# LoRa-E5_mini_v1_0.net
KiCad netlist of a schematic drawn in EAGLE
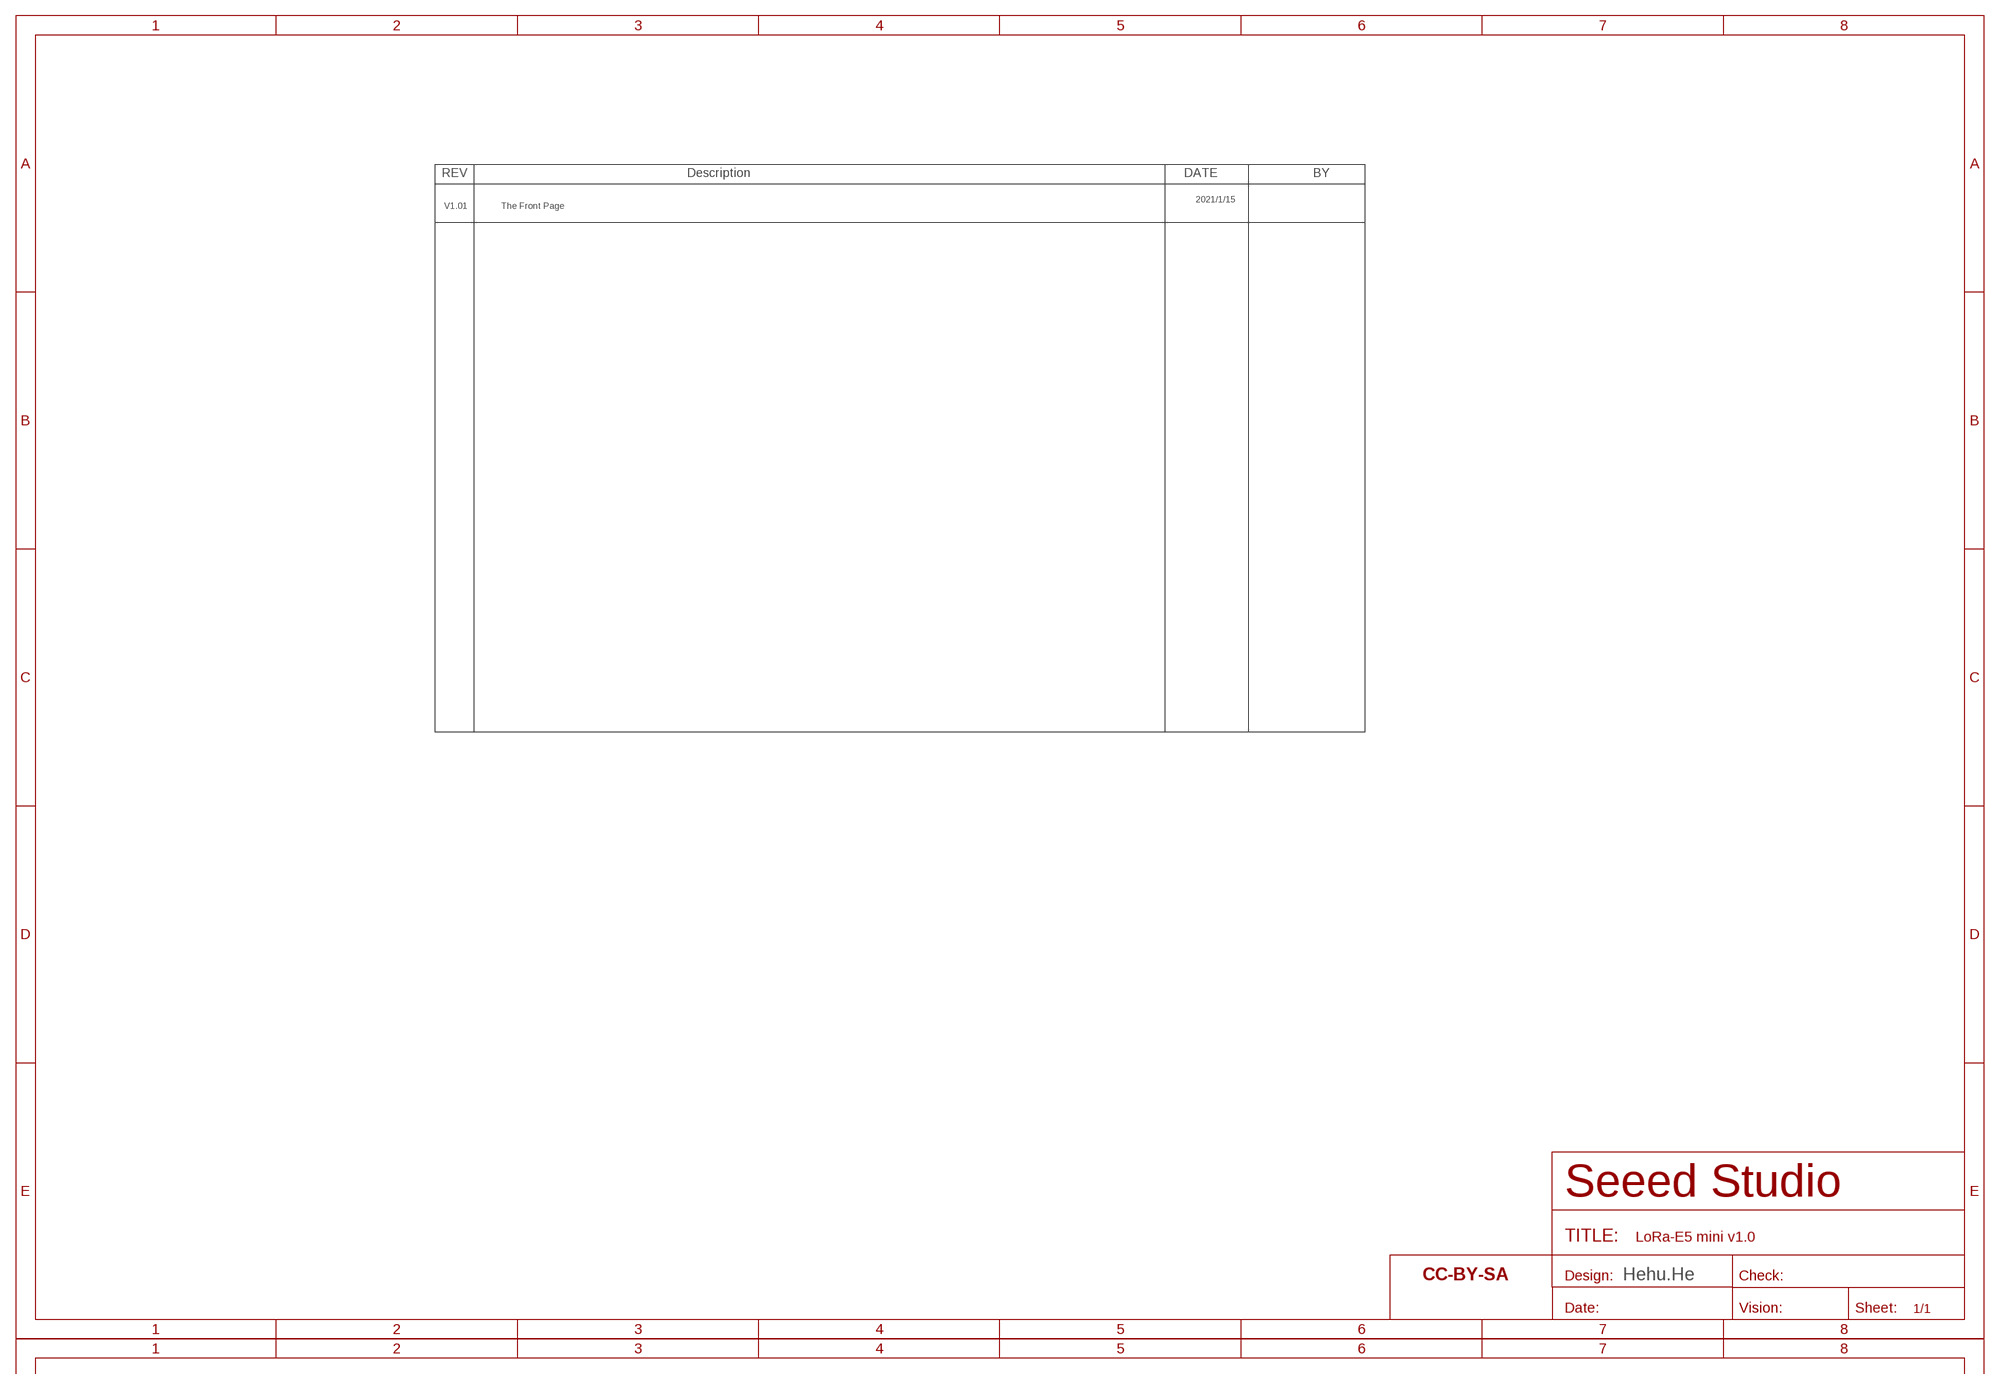
[diagram p0: schematic, sheet 1, part 1 of 2]
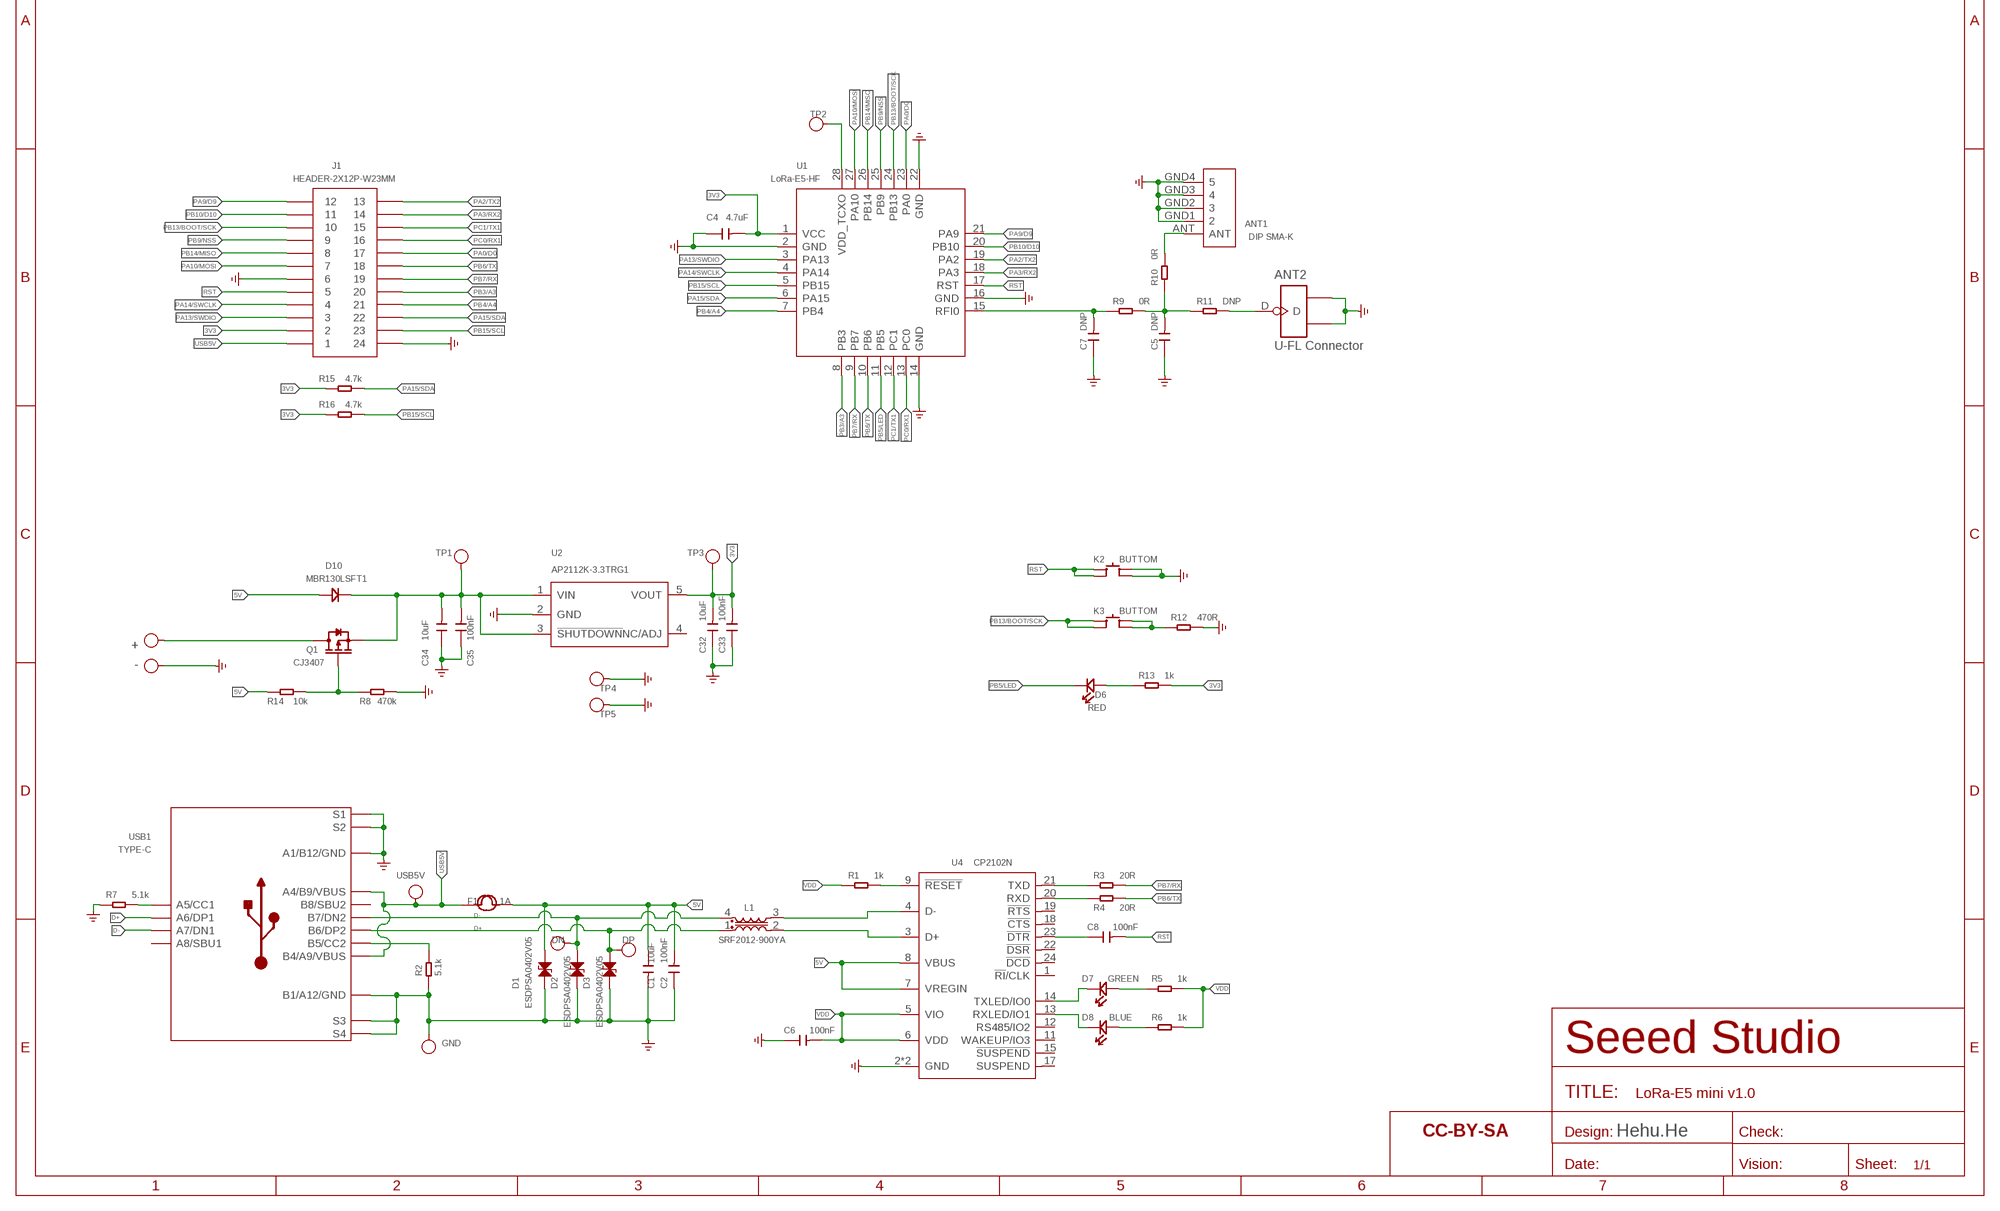
[diagram p1: schematic, sheet 1, part 2 of 2]

(export (version "E")
  (design (tool "Eeschema 10.0.6"))
  (components
    (comp (ref "+")
      (value "TEST-POINT-D65/35")
      (footprint "eagle-import:TP-D65_35MIL")
      (libsource (lib "eagle-import") (part "TEST-POINT-D65/35"))
    )
    (comp (ref "-")
      (value "TEST-POINT-D65/35")
      (footprint "eagle-import:TP-D65_35MIL")
      (libsource (lib "eagle-import") (part "TEST-POINT-D65/35"))
    )
    (comp (ref "ANT1")
      (value "DIP SMA-K")
      (footprint "eagle-import:SMA5P-SMD-5.1-6.5X6.5X16.5MM")
      (libsource (lib "eagle-import") (part "ANTENNA-SMA-MCX-JE-320160125"))
    )
    (comp (ref "ANT2")
      (value "U-FL Connector")
      (footprint "eagle-import:U-FL3P-SMD-2.6X2.6X1.0MM")
      (libsource (lib "eagle-import") (part "ANTENNA-U-FL-320110048"))
    )
    (comp (ref "C1")
      (value "10uF")
      (footprint "eagle-import:C0603")
      (libsource (lib "eagle-import") (part "CAP-0603"))
    )
    (comp (ref "C2")
      (value "100nF")
      (footprint "eagle-import:C0402")
      (libsource (lib "eagle-import") (part "CAP-0402"))
    )
    (comp (ref "C4")
      (value "4.7uF")
      (footprint "eagle-import:C0603")
      (libsource (lib "eagle-import") (part "CAP-0603"))
    )
    (comp (ref "C5")
      (value "DNP")
      (footprint "eagle-import:C0402")
      (libsource (lib "eagle-import") (part "CAP-0402"))
    )
    (comp (ref "C6")
      (value "100nF")
      (footprint "eagle-import:C0402")
      (libsource (lib "eagle-import") (part "CAP-0402"))
    )
    (comp (ref "C7")
      (value "DNP")
      (footprint "eagle-import:C0402")
      (libsource (lib "eagle-import") (part "CAP-0402"))
    )
    (comp (ref "C8")
      (value "100nF")
      (footprint "eagle-import:C0402")
      (libsource (lib "eagle-import") (part "CAP-0402"))
    )
    (comp (ref "C32")
      (value "10uF")
      (footprint "eagle-import:C0805")
      (libsource (lib "eagle-import") (part "CAP-0805"))
    )
    (comp (ref "C33")
      (value "100nF")
      (footprint "eagle-import:C0603")
      (libsource (lib "eagle-import") (part "CAP-0603"))
    )
    (comp (ref "C34")
      (value "10uF")
      (footprint "eagle-import:C0805")
      (libsource (lib "eagle-import") (part "CAP-0805"))
    )
    (comp (ref "C35")
      (value "100nF")
      (footprint "eagle-import:C0603")
      (libsource (lib "eagle-import") (part "CAP-0603"))
    )
    (comp (ref "D1")
      (value "ESDPSA0402V05")
      (footprint "eagle-import:ESD-0402")
      (libsource (lib "eagle-import") (part "D-ESD-2P-DOUBLE-0402"))
    )
    (comp (ref "D2")
      (value "ESDPSA0402V05")
      (footprint "eagle-import:ESD-0402")
      (libsource (lib "eagle-import") (part "D-ESD-2P-DOUBLE-0402"))
    )
    (comp (ref "D3")
      (value "ESDPSA0402V05")
      (footprint "eagle-import:ESD-0402")
      (libsource (lib "eagle-import") (part "D-ESD-2P-DOUBLE-0402"))
    )
    (comp (ref "D6")
      (value "RED")
      (footprint "eagle-import:LED-0603")
      (libsource (lib "eagle-import") (part "LED'0603'"))
    )
    (comp (ref "D7")
      (value "GREEN")
      (footprint "eagle-import:LED-0603")
      (libsource (lib "eagle-import") (part "LED'0603'"))
    )
    (comp (ref "D8")
      (value "BLUE")
      (footprint "eagle-import:LED-0603")
      (libsource (lib "eagle-import") (part "LED'0603'"))
    )
    (comp (ref "D10")
      (value "MBR130LSFT1")
      (footprint "eagle-import:SOD-123")
      (libsource (lib "eagle-import") (part "DIODE'1206'"))
    )
    (comp (ref "DN")
      (value "TEST")
      (footprint "eagle-import:TP-D45MIL")
      (fields (field (name "PARTNO") "DNP"))
      (libsource (lib "eagle-import") (part "TEST-POINT'4545'"))
    )
    (comp (ref "DP")
      (value "TEST")
      (footprint "eagle-import:TP-D45MIL")
      (fields (field (name "PARTNO") "DNP"))
      (libsource (lib "eagle-import") (part "TEST-POINT'4545'"))
    )
    (comp (ref "F1")
      (value "1A")
      (footprint "eagle-import:F1206")
      (libsource (lib "eagle-import") (part "FUSE'1206'"))
    )
    (comp (ref "GND")
      (value "TEST")
      (footprint "eagle-import:TP-D45MIL")
      (fields (field (name "PARTNO") "DNP"))
      (libsource (lib "eagle-import") (part "TEST-POINT'4545'"))
    )
    (comp (ref "J1")
      (value "HEADER-2X12P-W23MM")
      (footprint "eagle-import:H2X12-2.54-23MM")
      (libsource (lib "eagle-import") (part "HEADER-2X12P-W23MM"))
    )
    (comp (ref "K2")
      (value "BUTTOM")
      (footprint "eagle-import:SW4P-SMD-4.5X3.2X2.5MM")
      (libsource (lib "eagle-import") (part "BUTTON-4P-4.5X3.2"))
    )
    (comp (ref "K3")
      (value "BUTTOM")
      (footprint "eagle-import:SW4P-SMD-4.5X3.2X2.5MM")
      (libsource (lib "eagle-import") (part "BUTTON-4P-4.5X3.2"))
    )
    (comp (ref "L1")
      (value "SRF2012-900YA")
      (footprint "eagle-import:INT4-0.85-2X1.25X1.2MM")
      (libsource (lib "eagle-import") (part "INDUCTOR-COMMON-MODE-SRF2012-900YA"))
    )
    (comp (ref "Q1")
      (value "CJ3407")
      (footprint "eagle-import:SOT-23")
      (libsource (lib "eagle-import") (part "MOSFET-P'SI2323CDS/SI2305DS{lt}BR{gt}'"))
    )
    (comp (ref "R1")
      (value "1k")
      (footprint "eagle-import:R0402")
      (libsource (lib "eagle-import") (part "RES-0402"))
    )
    (comp (ref "R2")
      (value "5.1k")
      (footprint "eagle-import:R0402")
      (libsource (lib "eagle-import") (part "RES-0402"))
    )
    (comp (ref "R3")
      (value "20R")
      (footprint "eagle-import:R0402")
      (libsource (lib "eagle-import") (part "RES-0402"))
    )
    (comp (ref "R4")
      (value "20R")
      (footprint "eagle-import:R0402")
      (libsource (lib "eagle-import") (part "RES-0402"))
    )
    (comp (ref "R5")
      (value "1k")
      (footprint "eagle-import:R0402")
      (libsource (lib "eagle-import") (part "RES-0402"))
    )
    (comp (ref "R6")
      (value "1k")
      (footprint "eagle-import:R0402")
      (libsource (lib "eagle-import") (part "RES-0402"))
    )
    (comp (ref "R7")
      (value "5.1k")
      (footprint "eagle-import:R0402")
      (libsource (lib "eagle-import") (part "RES-0402"))
    )
    (comp (ref "R8")
      (value "470k")
      (footprint "eagle-import:R0402")
      (libsource (lib "eagle-import") (part "RES-0402"))
    )
    (comp (ref "R9")
      (value "0R")
      (footprint "eagle-import:R0402")
      (libsource (lib "eagle-import") (part "RES-0402"))
    )
    (comp (ref "R10")
      (value "0R")
      (footprint "eagle-import:R0402")
      (libsource (lib "eagle-import") (part "RES-0402"))
    )
    (comp (ref "R11")
      (value "DNP")
      (footprint "eagle-import:R0402")
      (libsource (lib "eagle-import") (part "RES-0402"))
    )
    (comp (ref "R12")
      (value "470R")
      (footprint "eagle-import:R0402")
      (libsource (lib "eagle-import") (part "RES-0402"))
    )
    (comp (ref "R13")
      (value "1k")
      (footprint "eagle-import:R0402")
      (libsource (lib "eagle-import") (part "RES-0402"))
    )
    (comp (ref "R14")
      (value "10k")
      (footprint "eagle-import:R0402")
      (libsource (lib "eagle-import") (part "RES-0402"))
    )
    (comp (ref "R15")
      (value "4.7k")
      (footprint "eagle-import:R0402")
      (libsource (lib "eagle-import") (part "RES-0402"))
    )
    (comp (ref "R16")
      (value "4.7k")
      (footprint "eagle-import:R0402")
      (libsource (lib "eagle-import") (part "RES-0402"))
    )
    (comp (ref "TP1")
      (value "TEST")
      (footprint "eagle-import:TP-D45MIL")
      (fields (field (name "PARTNO") "DNP"))
      (libsource (lib "eagle-import") (part "TEST-POINT'4545'"))
    )
    (comp (ref "TP2")
      (value "TEST")
      (footprint "eagle-import:TP-D45MIL")
      (fields (field (name "PARTNO") "DNP"))
      (libsource (lib "eagle-import") (part "TEST-POINT'4545'"))
    )
    (comp (ref "TP3")
      (value "TEST")
      (footprint "eagle-import:TP-D45MIL")
      (fields (field (name "PARTNO") "DNP"))
      (libsource (lib "eagle-import") (part "TEST-POINT'4545'"))
    )
    (comp (ref "TP4")
      (value "TEST-POINT-23")
      (footprint "eagle-import:TP-D23MIL")
      (libsource (lib "eagle-import") (part "TEST-POINT-23"))
    )
    (comp (ref "TP5")
      (value "TEST-POINT-23")
      (footprint "eagle-import:TP-D23MIL")
      (libsource (lib "eagle-import") (part "TEST-POINT-23"))
    )
    (comp (ref "U1")
      (value "LoRa-E5-HF")
      (footprint "eagle-import:MOUDLE28P-1.25-12X12X2.5MM")
      (libsource (lib "eagle-import") (part "MOUDLE_LORA_E5"))
    )
    (comp (ref "U2")
      (value "AP2112K-3.3TRG1")
      (footprint "eagle-import:SOT-23-5")
      (libsource (lib "eagle-import") (part "PMIC-AP2127"))
    )
    (comp (ref "U4")
      (value "CP2102N")
      (footprint "eagle-import:QFN24G-0.5-4X4MM")
      (libsource (lib "eagle-import") (part "CONVERTER-CP2102N(QFN24)"))
    )
    (comp (ref "USB1")
      (value "TYPE-C")
      (footprint "eagle-import:USB2.0-TYPE-C")
      (libsource (lib "eagle-import") (part "USB2.0-TYPE-C-320010698"))
    )
    (comp (ref "USB5V")
      (value "TEST")
      (footprint "eagle-import:TP-D45MIL")
      (fields (field (name "PARTNO") "DNP"))
      (libsource (lib "eagle-import") (part "TEST-POINT'4545'"))
    )
  )
  (nets
    (net (code "1") (name "3V3") (class "Default")
      (node (ref "C32") (pin "2") (pinfunction "2_2") (pintype "passive"))
      (node (ref "C33") (pin "2") (pinfunction "2_2") (pintype "passive"))
      (node (ref "C4") (pin "2") (pinfunction "2_2") (pintype "passive"))
      (node (ref "J1") (pin "A2") (pinfunction "2_A2") (pintype "bidirectional"))
      (node (ref "J1") (pin "B2") (pinfunction "2_B2") (pintype "bidirectional"))
      (node (ref "J1") (pin "E2") (pinfunction "2_E2") (pintype "bidirectional"))
      (node (ref "J1") (pin "F2") (pinfunction "2_F2") (pintype "bidirectional"))
      (node (ref "R13") (pin "2") (pinfunction "2_2") (pintype "passive"))
      (node (ref "R15") (pin "1") (pinfunction "1_1") (pintype "passive"))
      (node (ref "R16") (pin "1") (pinfunction "1_1") (pintype "passive"))
      (node (ref "TP3") (pin "T") (pinfunction "T_T") (pintype "bidirectional"))
      (node (ref "U1") (pin "1") (pinfunction "VCC_1") (pintype "bidirectional"))
      (node (ref "U2") (pin "5") (pinfunction "VOUT_5") (pintype "bidirectional"))
    )
    (net (code "2") (name "5V") (class "Default")
      (node (ref "C1") (pin "1") (pinfunction "1_1") (pintype "passive"))
      (node (ref "C2") (pin "2") (pinfunction "2_2") (pintype "passive"))
      (node (ref "D1") (pin "2") (pinfunction "2_2") (pintype "bidirectional"))
      (node (ref "D10") (pin "+") (pinfunction "+_+") (pintype "passive"))
      (node (ref "F1") (pin "2") (pinfunction "2_2") (pintype "bidirectional"))
      (node (ref "R14") (pin "1") (pinfunction "1_1") (pintype "passive"))
      (node (ref "U4") (pin "7") (pinfunction "VREGIN_7") (pintype "bidirectional"))
      (node (ref "U4") (pin "8") (pinfunction "VBUS_8") (pintype "bidirectional"))
    )
    (net (code "3") (name "D+") (class "Default")
      (node (ref "D3") (pin "2") (pinfunction "2_2") (pintype "bidirectional"))
      (node (ref "DP") (pin "T") (pinfunction "T_T") (pintype "bidirectional"))
      (node (ref "L1") (pin "1") (pinfunction "1_1") (pintype "bidirectional"))
      (node (ref "USB1") (pin "A6") (pinfunction "A6/DP1_A6") (pintype "bidirectional"))
      (node (ref "USB1") (pin "B6") (pinfunction "B6/DP2_B6") (pintype "bidirectional"))
    )
    (net (code "4") (name "D-") (class "Default")
      (node (ref "D2") (pin "2") (pinfunction "2_2") (pintype "bidirectional"))
      (node (ref "DN") (pin "T") (pinfunction "T_T") (pintype "bidirectional"))
      (node (ref "L1") (pin "4") (pinfunction "4_4") (pintype "bidirectional"))
      (node (ref "USB1") (pin "A7") (pinfunction "A7/DN1_A7") (pintype "bidirectional"))
      (node (ref "USB1") (pin "B7") (pinfunction "B7/DN2_B7") (pintype "bidirectional"))
    )
    (net (code "5") (name "GND_POWER") (class "Default")
      (node (ref "-") (pin "P1") (pinfunction "T_P1") (pintype "bidirectional"))
      (node (ref "ANT1") (pin "GND1") (pinfunction "2_GND1") (pintype "bidirectional"))
      (node (ref "ANT1") (pin "GND2") (pinfunction "3_GND2") (pintype "bidirectional"))
      (node (ref "ANT1") (pin "GND3") (pinfunction "4_GND3") (pintype "bidirectional"))
      (node (ref "ANT1") (pin "GND4") (pinfunction "5_GND4") (pintype "bidirectional"))
      (node (ref "ANT2") (pin "GND1") (pinfunction "GND1_GND1") (pintype "bidirectional"))
      (node (ref "ANT2") (pin "GND2") (pinfunction "GND2_GND2") (pintype "bidirectional"))
      (node (ref "C1") (pin "2") (pinfunction "2_2") (pintype "passive"))
      (node (ref "C2") (pin "1") (pinfunction "1_1") (pintype "passive"))
      (node (ref "C32") (pin "1") (pinfunction "1_1") (pintype "passive"))
      (node (ref "C33") (pin "1") (pinfunction "1_1") (pintype "passive"))
      (node (ref "C34") (pin "1") (pinfunction "1_1") (pintype "passive"))
      (node (ref "C35") (pin "1") (pinfunction "1_1") (pintype "passive"))
      (node (ref "C4") (pin "1") (pinfunction "1_1") (pintype "passive"))
      (node (ref "C5") (pin "1") (pinfunction "1_1") (pintype "passive"))
      (node (ref "C6") (pin "1") (pinfunction "1_1") (pintype "passive"))
      (node (ref "C7") (pin "1") (pinfunction "1_1") (pintype "passive"))
      (node (ref "D1") (pin "1") (pinfunction "1_1") (pintype "bidirectional"))
      (node (ref "D2") (pin "1") (pinfunction "1_1") (pintype "bidirectional"))
      (node (ref "D3") (pin "1") (pinfunction "1_1") (pintype "bidirectional"))
      (node (ref "GND") (pin "T") (pinfunction "T_T") (pintype "bidirectional"))
      (node (ref "J1") (pin "A6") (pinfunction "6_A6") (pintype "bidirectional"))
      (node (ref "J1") (pin "B6") (pinfunction "6_B6") (pintype "bidirectional"))
      (node (ref "J1") (pin "C12") (pinfunction "24_C12") (pintype "bidirectional"))
      (node (ref "J1") (pin "D12") (pinfunction "24_D12") (pintype "bidirectional"))
      (node (ref "J1") (pin "E24") (pinfunction "24_E24") (pintype "bidirectional"))
      (node (ref "J1") (pin "E6") (pinfunction "6_E6") (pintype "bidirectional"))
      (node (ref "J1") (pin "F24") (pinfunction "24_F24") (pintype "bidirectional"))
      (node (ref "J1") (pin "F6") (pinfunction "6_F6") (pintype "bidirectional"))
      (node (ref "K2") (pin "3") (pinfunction "B0_3") (pintype "bidirectional"))
      (node (ref "K2") (pin "4") (pinfunction "B1_4") (pintype "bidirectional"))
      (node (ref "R12") (pin "2") (pinfunction "2_2") (pintype "passive"))
      (node (ref "R2") (pin "1") (pinfunction "1_1") (pintype "passive"))
      (node (ref "R7") (pin "1") (pinfunction "1_1") (pintype "passive"))
      (node (ref "R8") (pin "1") (pinfunction "1_1") (pintype "passive"))
      (node (ref "TP4") (pin "T") (pinfunction "T_T") (pintype "bidirectional"))
      (node (ref "TP5") (pin "T") (pinfunction "T_T") (pintype "bidirectional"))
      (node (ref "U1") (pin "14") (pinfunction "GND_14") (pintype "bidirectional"))
      (node (ref "U1") (pin "16") (pinfunction "GND_16") (pintype "bidirectional"))
      (node (ref "U1") (pin "2") (pinfunction "GND_2") (pintype "bidirectional"))
      (node (ref "U1") (pin "22") (pinfunction "GND_22") (pintype "bidirectional"))
      (node (ref "U2") (pin "2") (pinfunction "GND_2") (pintype "bidirectional"))
      (node (ref "U4") (pin "2") (pinfunction "GND_2") (pintype "bidirectional"))
      (node (ref "U4") (pin "PAD") (pinfunction "GND_PAD") (pintype "bidirectional"))
      (node (ref "USB1") (pin "A1_B12") (pinfunction "A1/B12/GND_A1_B12") (pintype "bidirectional"))
      (node (ref "USB1") (pin "B1_A12") (pinfunction "B1/A12/GND_B1_A12") (pintype "bidirectional"))
      (node (ref "USB1") (pin "S1") (pinfunction "S1_S1") (pintype "bidirectional"))
      (node (ref "USB1") (pin "S2") (pinfunction "S2_S2") (pintype "bidirectional"))
      (node (ref "USB1") (pin "S3") (pinfunction "S3_S3") (pintype "bidirectional"))
      (node (ref "USB1") (pin "S4") (pinfunction "S4_S4") (pintype "bidirectional"))
      (node (ref "USB1") (pin "S5") (pinfunction "S1_S5") (pintype "bidirectional"))
      (node (ref "USB1") (pin "S6") (pinfunction "S2_S6") (pintype "bidirectional"))
    )
    (net (code "6") (name "Net-(+-T)") (class "Default")
      (node (ref "+") (pin "P1") (pinfunction "T_P1") (pintype "bidirectional"))
      (node (ref "Q1") (pin "3") (pinfunction "D_3") (pintype "passive"))
    )
    (net (code "7") (name "Net-(ANT1-PadANT)") (class "Default")
      (node (ref "ANT1") (pin "ANT") (pinfunction "ANT_ANT") (pintype "bidirectional"))
      (node (ref "R10") (pin "2") (pinfunction "2_2") (pintype "passive"))
    )
    (net (code "8") (name "Net-(ANT2-PadD)") (class "Default")
      (node (ref "ANT2") (pin "D") (pinfunction "D_D") (pintype "bidirectional"))
      (node (ref "R11") (pin "2") (pinfunction "2_2") (pintype "passive"))
    )
    (net (code "9") (name "Net-(C5-Pad2)") (class "Default")
      (node (ref "C5") (pin "2") (pinfunction "2_2") (pintype "passive"))
      (node (ref "R10") (pin "1") (pinfunction "1_1") (pintype "passive"))
      (node (ref "R11") (pin "1") (pinfunction "1_1") (pintype "passive"))
      (node (ref "R9") (pin "2") (pinfunction "2_2") (pintype "passive"))
    )
    (net (code "10") (name "Net-(D6-Pad+)") (class "Default")
      (node (ref "D6") (pin "+") (pinfunction "+_+") (pintype "passive"))
      (node (ref "R13") (pin "1") (pinfunction "1_1") (pintype "passive"))
    )
    (net (code "11") (name "Net-(D7-Pad+)") (class "Default")
      (node (ref "D7") (pin "+") (pinfunction "+_+") (pintype "passive"))
      (node (ref "R5") (pin "1") (pinfunction "1_1") (pintype "passive"))
    )
    (net (code "12") (name "Net-(D8-Pad+)") (class "Default")
      (node (ref "D8") (pin "+") (pinfunction "+_+") (pintype "passive"))
      (node (ref "R6") (pin "1") (pinfunction "1_1") (pintype "passive"))
    )
    (net (code "13") (name "Net-(K3-B0)") (class "Default")
      (node (ref "K3") (pin "3") (pinfunction "B0_3") (pintype "bidirectional"))
      (node (ref "K3") (pin "4") (pinfunction "B1_4") (pintype "bidirectional"))
      (node (ref "R12") (pin "1") (pinfunction "1_1") (pintype "passive"))
    )
    (net (code "14") (name "Net-(Q1-G)") (class "Default")
      (node (ref "Q1") (pin "1") (pinfunction "G_1") (pintype "passive"))
      (node (ref "R14") (pin "2") (pinfunction "2_2") (pintype "passive"))
      (node (ref "R8") (pin "2") (pinfunction "2_2") (pintype "passive"))
    )
    (net (code "15") (name "Net-(Q1-S)") (class "Default")
      (node (ref "C34") (pin "2") (pinfunction "2_2") (pintype "passive"))
      (node (ref "C35") (pin "2") (pinfunction "2_2") (pintype "passive"))
      (node (ref "D10") (pin "-") (pinfunction "-_-") (pintype "passive"))
      (node (ref "Q1") (pin "2") (pinfunction "S_2") (pintype "passive"))
      (node (ref "TP1") (pin "T") (pinfunction "T_T") (pintype "bidirectional"))
      (node (ref "U2") (pin "1") (pinfunction "VIN_1") (pintype "bidirectional"))
      (node (ref "U2") (pin "3") (pinfunction "~{SHUTDOWN}_3") (pintype "bidirectional"))
    )
    (net (code "16") (name "Net-(U1-RFI0)") (class "Default")
      (node (ref "C7") (pin "2") (pinfunction "2_2") (pintype "passive"))
      (node (ref "R9") (pin "1") (pinfunction "1_1") (pintype "passive"))
      (node (ref "U1") (pin "15") (pinfunction "RFI0_15") (pintype "bidirectional"))
    )
    (net (code "17") (name "Net-(U1-VDD_TCXO)") (class "Default")
      (node (ref "TP2") (pin "T") (pinfunction "T_T") (pintype "bidirectional"))
      (node (ref "U1") (pin "28") (pinfunction "VDD_TCXO_28") (pintype "bidirectional"))
    )
    (net (code "18") (name "Net-(U4-D+)") (class "Default")
      (node (ref "L1") (pin "2") (pinfunction "2_2") (pintype "bidirectional"))
      (node (ref "U4") (pin "3") (pinfunction "D+_3") (pintype "bidirectional"))
    )
    (net (code "19") (name "Net-(U4-D-)") (class "Default")
      (node (ref "L1") (pin "3") (pinfunction "3_3") (pintype "bidirectional"))
      (node (ref "U4") (pin "4") (pinfunction "D-_4") (pintype "bidirectional"))
    )
    (net (code "20") (name "Net-(U4-RXD)") (class "Default")
      (node (ref "R4") (pin "1") (pinfunction "1_1") (pintype "passive"))
      (node (ref "U4") (pin "20") (pinfunction "RXD_20") (pintype "bidirectional"))
    )
    (net (code "21") (name "Net-(U4-RXLED{slash}IO1)") (class "Default")
      (node (ref "D8") (pin "-") (pinfunction "-_-") (pintype "passive"))
      (node (ref "U4") (pin "13") (pinfunction "RXLED/IO1_13") (pintype "bidirectional"))
    )
    (net (code "22") (name "Net-(U4-TXD)") (class "Default")
      (node (ref "R3") (pin "1") (pinfunction "1_1") (pintype "passive"))
      (node (ref "U4") (pin "21") (pinfunction "TXD_21") (pintype "bidirectional"))
    )
    (net (code "23") (name "Net-(U4-TXLED{slash}IO0)") (class "Default")
      (node (ref "D7") (pin "-") (pinfunction "-_-") (pintype "passive"))
      (node (ref "U4") (pin "14") (pinfunction "TXLED/IO0_14") (pintype "bidirectional"))
    )
    (net (code "24") (name "Net-(U4-~{DTR})") (class "Default")
      (node (ref "C8") (pin "1") (pinfunction "1_1") (pintype "passive"))
      (node (ref "U4") (pin "23") (pinfunction "~{DTR}_23") (pintype "bidirectional"))
    )
    (net (code "25") (name "Net-(U4-~{RESET})") (class "Default")
      (node (ref "R1") (pin "2") (pinfunction "2_2") (pintype "passive"))
      (node (ref "U4") (pin "9") (pinfunction "~{RESET}_9") (pintype "bidirectional"))
    )
    (net (code "26") (name "Net-(USB1-A5{slash}CC1)") (class "Default")
      (node (ref "R7") (pin "2") (pinfunction "2_2") (pintype "passive"))
      (node (ref "USB1") (pin "A5") (pinfunction "A5/CC1_A5") (pintype "bidirectional"))
    )
    (net (code "27") (name "Net-(USB1-B5{slash}CC2)") (class "Default")
      (node (ref "R2") (pin "2") (pinfunction "2_2") (pintype "passive"))
      (node (ref "USB1") (pin "B5") (pinfunction "B5/CC2_B5") (pintype "bidirectional"))
    )
    (net (code "28") (name "PA0{slash}D0") (class "Default")
      (node (ref "J1") (pin "C5") (pinfunction "17_C5") (pintype "bidirectional"))
      (node (ref "J1") (pin "D5") (pinfunction "17_D5") (pintype "bidirectional"))
      (node (ref "J1") (pin "E17") (pinfunction "17_E17") (pintype "bidirectional"))
      (node (ref "J1") (pin "F17") (pinfunction "17_F17") (pintype "bidirectional"))
      (node (ref "U1") (pin "23") (pinfunction "PA0_23") (pintype "bidirectional"))
    )
    (net (code "29") (name "PA2{slash}TX2") (class "Default")
      (node (ref "J1") (pin "C1") (pinfunction "13_C1") (pintype "bidirectional"))
      (node (ref "J1") (pin "D1") (pinfunction "13_D1") (pintype "bidirectional"))
      (node (ref "J1") (pin "E13") (pinfunction "13_E13") (pintype "bidirectional"))
      (node (ref "J1") (pin "F13") (pinfunction "13_F13") (pintype "bidirectional"))
      (node (ref "U1") (pin "19") (pinfunction "PA2_19") (pintype "bidirectional"))
    )
    (net (code "30") (name "PA3{slash}RX2") (class "Default")
      (node (ref "J1") (pin "C2") (pinfunction "14_C2") (pintype "bidirectional"))
      (node (ref "J1") (pin "D2") (pinfunction "14_D2") (pintype "bidirectional"))
      (node (ref "J1") (pin "E14") (pinfunction "14_E14") (pintype "bidirectional"))
      (node (ref "J1") (pin "F14") (pinfunction "14_F14") (pintype "bidirectional"))
      (node (ref "U1") (pin "18") (pinfunction "PA3_18") (pintype "bidirectional"))
    )
    (net (code "31") (name "PA9{slash}D9") (class "Default")
      (node (ref "J1") (pin "A12") (pinfunction "12_A12") (pintype "bidirectional"))
      (node (ref "J1") (pin "B12") (pinfunction "12_B12") (pintype "bidirectional"))
      (node (ref "J1") (pin "E12") (pinfunction "12_E12") (pintype "bidirectional"))
      (node (ref "J1") (pin "F12") (pinfunction "12_F12") (pintype "bidirectional"))
      (node (ref "U1") (pin "21") (pinfunction "PA9_21") (pintype "bidirectional"))
    )
    (net (code "32") (name "PA10{slash}MOSI") (class "Default")
      (node (ref "J1") (pin "A7") (pinfunction "7_A7") (pintype "bidirectional"))
      (node (ref "J1") (pin "B7") (pinfunction "7_B7") (pintype "bidirectional"))
      (node (ref "J1") (pin "E7") (pinfunction "7_E7") (pintype "bidirectional"))
      (node (ref "J1") (pin "F7") (pinfunction "7_F7") (pintype "bidirectional"))
      (node (ref "U1") (pin "27") (pinfunction "PA10_27") (pintype "bidirectional"))
    )
    (net (code "33") (name "PA13{slash}SWDIO") (class "Default")
      (node (ref "J1") (pin "A3") (pinfunction "3_A3") (pintype "bidirectional"))
      (node (ref "J1") (pin "B3") (pinfunction "3_B3") (pintype "bidirectional"))
      (node (ref "J1") (pin "E3") (pinfunction "3_E3") (pintype "bidirectional"))
      (node (ref "J1") (pin "F3") (pinfunction "3_F3") (pintype "bidirectional"))
      (node (ref "U1") (pin "3") (pinfunction "PA13_3") (pintype "bidirectional"))
    )
    (net (code "34") (name "PA14{slash}SWCLK") (class "Default")
      (node (ref "J1") (pin "A4") (pinfunction "4_A4") (pintype "bidirectional"))
      (node (ref "J1") (pin "B4") (pinfunction "4_B4") (pintype "bidirectional"))
      (node (ref "J1") (pin "E4") (pinfunction "4_E4") (pintype "bidirectional"))
      (node (ref "J1") (pin "F4") (pinfunction "4_F4") (pintype "bidirectional"))
      (node (ref "U1") (pin "4") (pinfunction "PA14_4") (pintype "bidirectional"))
    )
    (net (code "35") (name "PA15{slash}SDA") (class "Default")
      (node (ref "J1") (pin "C10") (pinfunction "22_C10") (pintype "bidirectional"))
      (node (ref "J1") (pin "D10") (pinfunction "22_D10") (pintype "bidirectional"))
      (node (ref "J1") (pin "E22") (pinfunction "22_E22") (pintype "bidirectional"))
      (node (ref "J1") (pin "F22") (pinfunction "22_F22") (pintype "bidirectional"))
      (node (ref "R15") (pin "2") (pinfunction "2_2") (pintype "passive"))
      (node (ref "U1") (pin "6") (pinfunction "PA15_6") (pintype "bidirectional"))
    )
    (net (code "36") (name "PB3{slash}A3") (class "Default")
      (node (ref "J1") (pin "C8") (pinfunction "20_C8") (pintype "bidirectional"))
      (node (ref "J1") (pin "D8") (pinfunction "20_D8") (pintype "bidirectional"))
      (node (ref "J1") (pin "E20") (pinfunction "20_E20") (pintype "bidirectional"))
      (node (ref "J1") (pin "F20") (pinfunction "20_F20") (pintype "bidirectional"))
      (node (ref "U1") (pin "8") (pinfunction "PB3_8") (pintype "bidirectional"))
    )
    (net (code "37") (name "PB4{slash}A4") (class "Default")
      (node (ref "J1") (pin "C9") (pinfunction "21_C9") (pintype "bidirectional"))
      (node (ref "J1") (pin "D9") (pinfunction "21_D9") (pintype "bidirectional"))
      (node (ref "J1") (pin "E21") (pinfunction "21_E21") (pintype "bidirectional"))
      (node (ref "J1") (pin "F21") (pinfunction "21_F21") (pintype "bidirectional"))
      (node (ref "U1") (pin "7") (pinfunction "PB4_7") (pintype "bidirectional"))
    )
    (net (code "38") (name "PB5{slash}LED") (class "Default")
      (node (ref "D6") (pin "-") (pinfunction "-_-") (pintype "passive"))
      (node (ref "U1") (pin "11") (pinfunction "PB5_11") (pintype "bidirectional"))
    )
    (net (code "39") (name "PB6{slash}TX") (class "Default")
      (node (ref "J1") (pin "C6") (pinfunction "18_C6") (pintype "bidirectional"))
      (node (ref "J1") (pin "D6") (pinfunction "18_D6") (pintype "bidirectional"))
      (node (ref "J1") (pin "E18") (pinfunction "18_E18") (pintype "bidirectional"))
      (node (ref "J1") (pin "F18") (pinfunction "18_F18") (pintype "bidirectional"))
      (node (ref "R4") (pin "2") (pinfunction "2_2") (pintype "passive"))
      (node (ref "U1") (pin "10") (pinfunction "PB6_10") (pintype "bidirectional"))
    )
    (net (code "40") (name "PB7{slash}RX") (class "Default")
      (node (ref "J1") (pin "C7") (pinfunction "19_C7") (pintype "bidirectional"))
      (node (ref "J1") (pin "D7") (pinfunction "19_D7") (pintype "bidirectional"))
      (node (ref "J1") (pin "E19") (pinfunction "19_E19") (pintype "bidirectional"))
      (node (ref "J1") (pin "F19") (pinfunction "19_F19") (pintype "bidirectional"))
      (node (ref "R3") (pin "2") (pinfunction "2_2") (pintype "passive"))
      (node (ref "U1") (pin "9") (pinfunction "PB7_9") (pintype "bidirectional"))
    )
    (net (code "41") (name "PB9{slash}NSS") (class "Default")
      (node (ref "J1") (pin "A9") (pinfunction "9_A9") (pintype "bidirectional"))
      (node (ref "J1") (pin "B9") (pinfunction "9_B9") (pintype "bidirectional"))
      (node (ref "J1") (pin "E9") (pinfunction "9_E9") (pintype "bidirectional"))
      (node (ref "J1") (pin "F9") (pinfunction "9_F9") (pintype "bidirectional"))
      (node (ref "U1") (pin "25") (pinfunction "PB9_25") (pintype "bidirectional"))
    )
    (net (code "42") (name "PB10{slash}D10") (class "Default")
      (node (ref "J1") (pin "A11") (pinfunction "11_A11") (pintype "bidirectional"))
      (node (ref "J1") (pin "B11") (pinfunction "11_B11") (pintype "bidirectional"))
      (node (ref "J1") (pin "E11") (pinfunction "11_E11") (pintype "bidirectional"))
      (node (ref "J1") (pin "F11") (pinfunction "11_F11") (pintype "bidirectional"))
      (node (ref "U1") (pin "20") (pinfunction "PB10_20") (pintype "bidirectional"))
    )
    (net (code "43") (name "PB13{slash}BOOT{slash}SCK") (class "Default")
      (node (ref "J1") (pin "A10") (pinfunction "10_A10") (pintype "bidirectional"))
      (node (ref "J1") (pin "B10") (pinfunction "10_B10") (pintype "bidirectional"))
      (node (ref "J1") (pin "E10") (pinfunction "10_E10") (pintype "bidirectional"))
      (node (ref "J1") (pin "F10") (pinfunction "10_F10") (pintype "bidirectional"))
      (node (ref "K3") (pin "1") (pinfunction "A0_1") (pintype "bidirectional"))
      (node (ref "K3") (pin "2") (pinfunction "A1_2") (pintype "bidirectional"))
      (node (ref "U1") (pin "24") (pinfunction "PB13_24") (pintype "bidirectional"))
    )
    (net (code "44") (name "PB14{slash}MISO") (class "Default")
      (node (ref "J1") (pin "A8") (pinfunction "8_A8") (pintype "bidirectional"))
      (node (ref "J1") (pin "B8") (pinfunction "8_B8") (pintype "bidirectional"))
      (node (ref "J1") (pin "E8") (pinfunction "8_E8") (pintype "bidirectional"))
      (node (ref "J1") (pin "F8") (pinfunction "8_F8") (pintype "bidirectional"))
      (node (ref "U1") (pin "26") (pinfunction "PB14_26") (pintype "bidirectional"))
    )
    (net (code "45") (name "PB15{slash}SCL") (class "Default")
      (node (ref "J1") (pin "C11") (pinfunction "23_C11") (pintype "bidirectional"))
      (node (ref "J1") (pin "D11") (pinfunction "23_D11") (pintype "bidirectional"))
      (node (ref "J1") (pin "E23") (pinfunction "23_E23") (pintype "bidirectional"))
      (node (ref "J1") (pin "F23") (pinfunction "23_F23") (pintype "bidirectional"))
      (node (ref "R16") (pin "2") (pinfunction "2_2") (pintype "passive"))
      (node (ref "U1") (pin "5") (pinfunction "PB15_5") (pintype "bidirectional"))
    )
    (net (code "46") (name "PC0{slash}RX1") (class "Default")
      (node (ref "J1") (pin "C4") (pinfunction "16_C4") (pintype "bidirectional"))
      (node (ref "J1") (pin "D4") (pinfunction "16_D4") (pintype "bidirectional"))
      (node (ref "J1") (pin "E16") (pinfunction "16_E16") (pintype "bidirectional"))
      (node (ref "J1") (pin "F16") (pinfunction "16_F16") (pintype "bidirectional"))
      (node (ref "U1") (pin "13") (pinfunction "PC0_13") (pintype "bidirectional"))
    )
    (net (code "47") (name "PC1{slash}TX1") (class "Default")
      (node (ref "J1") (pin "C3") (pinfunction "15_C3") (pintype "bidirectional"))
      (node (ref "J1") (pin "D3") (pinfunction "15_D3") (pintype "bidirectional"))
      (node (ref "J1") (pin "E15") (pinfunction "15_E15") (pintype "bidirectional"))
      (node (ref "J1") (pin "F15") (pinfunction "15_F15") (pintype "bidirectional"))
      (node (ref "U1") (pin "12") (pinfunction "PC1_12") (pintype "bidirectional"))
    )
    (net (code "48") (name "RST") (class "Default")
      (node (ref "C8") (pin "2") (pinfunction "2_2") (pintype "passive"))
      (node (ref "J1") (pin "A5") (pinfunction "5_A5") (pintype "bidirectional"))
      (node (ref "J1") (pin "B5") (pinfunction "5_B5") (pintype "bidirectional"))
      (node (ref "J1") (pin "E5") (pinfunction "5_E5") (pintype "bidirectional"))
      (node (ref "J1") (pin "F5") (pinfunction "5_F5") (pintype "bidirectional"))
      (node (ref "K2") (pin "1") (pinfunction "A0_1") (pintype "bidirectional"))
      (node (ref "K2") (pin "2") (pinfunction "A1_2") (pintype "bidirectional"))
      (node (ref "U1") (pin "17") (pinfunction "RST_17") (pintype "bidirectional"))
    )
    (net (code "49") (name "USB5V") (class "Default")
      (node (ref "F1") (pin "1") (pinfunction "1_1") (pintype "bidirectional"))
      (node (ref "J1") (pin "A1") (pinfunction "1_A1") (pintype "bidirectional"))
      (node (ref "J1") (pin "B1") (pinfunction "1_B1") (pintype "bidirectional"))
      (node (ref "J1") (pin "E1") (pinfunction "1_E1") (pintype "bidirectional"))
      (node (ref "J1") (pin "F1") (pinfunction "1_F1") (pintype "bidirectional"))
      (node (ref "USB1") (pin "A4_B9") (pinfunction "A4/B9/VBUS_A4_B9") (pintype "bidirectional"))
      (node (ref "USB1") (pin "B4_A9") (pinfunction "B4/A9/VBUS_B4_A9") (pintype "bidirectional"))
      (node (ref "USB5V") (pin "T") (pinfunction "T_T") (pintype "bidirectional"))
    )
    (net (code "50") (name "VDD") (class "Default")
      (node (ref "C6") (pin "2") (pinfunction "2_2") (pintype "passive"))
      (node (ref "R1") (pin "1") (pinfunction "1_1") (pintype "passive"))
      (node (ref "R5") (pin "2") (pinfunction "2_2") (pintype "passive"))
      (node (ref "R6") (pin "2") (pinfunction "2_2") (pintype "passive"))
      (node (ref "U4") (pin "5") (pinfunction "VIO_5") (pintype "bidirectional"))
      (node (ref "U4") (pin "6") (pinfunction "VDD_6") (pintype "bidirectional"))
    )
    (net (code "51") (name "unconnected-(U2-NC{slash}ADJ-Pad4)") (class "Default")
      (node (ref "U2") (pin "4") (pinfunction "NC/ADJ_4") (pintype "bidirectional"))
    )
    (net (code "52") (name "unconnected-(U4-RS485{slash}IO2-Pad12)") (class "Default")
      (node (ref "U4") (pin "12") (pinfunction "RS485/IO2_12") (pintype "bidirectional"))
    )
    (net (code "53") (name "unconnected-(U4-SUSPEND-Pad17)") (class "Default")
      (node (ref "U4") (pin "17") (pinfunction "SUSPEND_17") (pintype "bidirectional"))
    )
    (net (code "54") (name "unconnected-(U4-WAKEUP{slash}IO3-Pad11)") (class "Default")
      (node (ref "U4") (pin "11") (pinfunction "WAKEUP/IO3_11") (pintype "bidirectional"))
    )
    (net (code "55") (name "unconnected-(U4-~{CTS}-Pad18)") (class "Default")
      (node (ref "U4") (pin "18") (pinfunction "~{CTS}_18") (pintype "bidirectional"))
    )
    (net (code "56") (name "unconnected-(U4-~{DCD}-Pad24)") (class "Default")
      (node (ref "U4") (pin "24") (pinfunction "~{DCD}_24") (pintype "bidirectional"))
    )
    (net (code "57") (name "unconnected-(U4-~{DSR}-Pad22)") (class "Default")
      (node (ref "U4") (pin "22") (pinfunction "~{DSR}_22") (pintype "bidirectional"))
    )
    (net (code "58") (name "unconnected-(U4-~{RI}{slash}CLK-Pad1)") (class "Default")
      (node (ref "U4") (pin "1") (pinfunction "~{RI}/CLK_1") (pintype "bidirectional"))
    )
    (net (code "59") (name "unconnected-(U4-~{RTS}-Pad19)") (class "Default")
      (node (ref "U4") (pin "19") (pinfunction "~{RTS}_19") (pintype "bidirectional"))
    )
    (net (code "60") (name "unconnected-(U4-~{SUSPEND}-Pad15)") (class "Default")
      (node (ref "U4") (pin "15") (pinfunction "~{SUSPEND}_15") (pintype "bidirectional"))
    )
    (net (code "61") (name "unconnected-(USB1-A8{slash}SBU1-PadA8)") (class "Default")
      (node (ref "USB1") (pin "A8") (pinfunction "A8/SBU1_A8") (pintype "bidirectional"))
    )
    (net (code "62") (name "unconnected-(USB1-B8{slash}SBU2-PadB8)") (class "Default")
      (node (ref "USB1") (pin "B8") (pinfunction "B8/SBU2_B8") (pintype "bidirectional"))
    )
  )
)
